# MUX.net
KiCad netlist of a schematic drawn in EAGLE
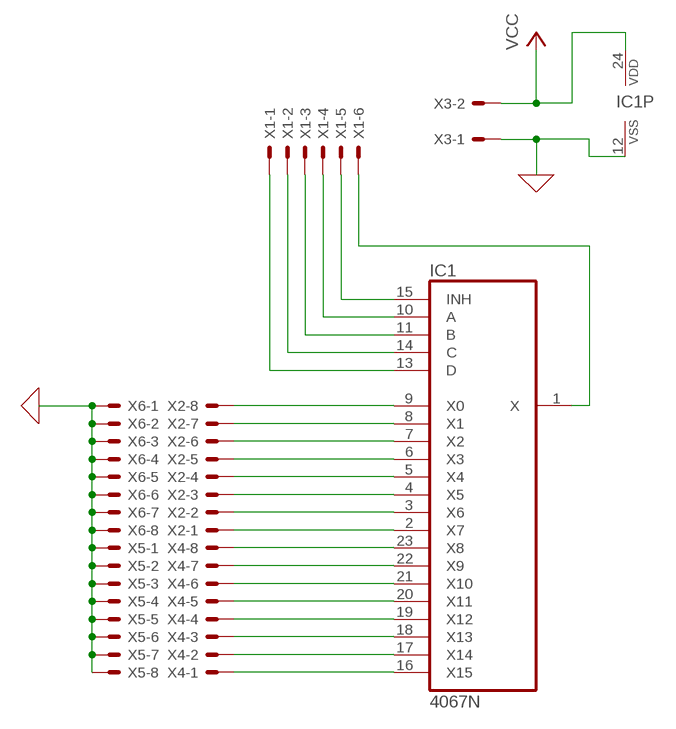
[diagram p0: schematic, sheet 1]

(export (version "E")
  (design (tool "Eeschema 10.0.6"))
  (components
    (comp (ref "IC1")
      (value "4067N")
      (footprint "eagle-import:DIL24-6")
      (libsource (lib "eagle-import") (part "4067N"))
    )
    (comp (ref "X1")
      (value "KK-156-6")
      (footprint "eagle-import:KK-156-6")
      (fields (field (name "MF") "MOLEX"))
      (libsource (lib "eagle-import") (part "KK-156-6"))
    )
    (comp (ref "X2")
      (value "KK-156-8")
      (footprint "eagle-import:KK-156-8")
      (fields (field (name "MF") "MOLEX"))
      (libsource (lib "eagle-import") (part "KK-156-8"))
    )
    (comp (ref "X3")
      (value "KK-156-2")
      (footprint "eagle-import:KK-156-2")
      (fields (field (name "MF") "MOLEX"))
      (libsource (lib "eagle-import") (part "KK-156-2"))
    )
    (comp (ref "X4")
      (value "KK-156-8")
      (footprint "eagle-import:KK-156-8")
      (fields (field (name "MF") "MOLEX"))
      (libsource (lib "eagle-import") (part "KK-156-8"))
    )
    (comp (ref "X5")
      (value "KK-156-8")
      (footprint "eagle-import:KK-156-8")
      (fields (field (name "MF") "MOLEX"))
      (libsource (lib "eagle-import") (part "KK-156-8"))
    )
    (comp (ref "X6")
      (value "KK-156-8")
      (footprint "eagle-import:KK-156-8")
      (fields (field (name "MF") "MOLEX"))
      (libsource (lib "eagle-import") (part "KK-156-8"))
    )
  )
  (nets
    (net (code "1") (name "GND") (class "Default")
      (node (ref "IC1") (pin "12") (pinfunction "VSS_12") (pintype "power_in"))
      (node (ref "X3") (pin "1") (pinfunction "S_1") (pintype "passive"))
      (node (ref "X5") (pin "1") (pinfunction "S_1") (pintype "passive"))
      (node (ref "X5") (pin "2") (pinfunction "S_2") (pintype "passive"))
      (node (ref "X5") (pin "3") (pinfunction "S_3") (pintype "passive"))
      (node (ref "X5") (pin "4") (pinfunction "S_4") (pintype "passive"))
      (node (ref "X5") (pin "5") (pinfunction "S_5") (pintype "passive"))
      (node (ref "X5") (pin "6") (pinfunction "S_6") (pintype "passive"))
      (node (ref "X5") (pin "7") (pinfunction "S_7") (pintype "passive"))
      (node (ref "X5") (pin "8") (pinfunction "S_8") (pintype "passive"))
      (node (ref "X6") (pin "1") (pinfunction "S_1") (pintype "passive"))
      (node (ref "X6") (pin "2") (pinfunction "S_2") (pintype "passive"))
      (node (ref "X6") (pin "3") (pinfunction "S_3") (pintype "passive"))
      (node (ref "X6") (pin "4") (pinfunction "S_4") (pintype "passive"))
      (node (ref "X6") (pin "5") (pinfunction "S_5") (pintype "passive"))
      (node (ref "X6") (pin "6") (pinfunction "S_6") (pintype "passive"))
      (node (ref "X6") (pin "7") (pinfunction "S_7") (pintype "passive"))
      (node (ref "X6") (pin "8") (pinfunction "S_8") (pintype "passive"))
    )
    (net (code "2") (name "Net-(IC1A-A)") (class "Default")
      (node (ref "IC1") (pin "10") (pinfunction "A_10") (pintype "input"))
      (node (ref "X1") (pin "4") (pinfunction "S_4") (pintype "passive"))
    )
    (net (code "3") (name "Net-(IC1A-B)") (class "Default")
      (node (ref "IC1") (pin "11") (pinfunction "B_11") (pintype "input"))
      (node (ref "X1") (pin "3") (pinfunction "S_3") (pintype "passive"))
    )
    (net (code "4") (name "Net-(IC1A-C)") (class "Default")
      (node (ref "IC1") (pin "14") (pinfunction "C_14") (pintype "input"))
      (node (ref "X1") (pin "2") (pinfunction "S_2") (pintype "passive"))
    )
    (net (code "5") (name "Net-(IC1A-D)") (class "Default")
      (node (ref "IC1") (pin "13") (pinfunction "D_13") (pintype "input"))
      (node (ref "X1") (pin "1") (pinfunction "S_1") (pintype "passive"))
    )
    (net (code "6") (name "Net-(IC1A-INH)") (class "Default")
      (node (ref "IC1") (pin "15") (pinfunction "INH_15") (pintype "input"))
      (node (ref "X1") (pin "5") (pinfunction "S_5") (pintype "passive"))
    )
    (net (code "7") (name "Net-(IC1A-X)") (class "Default")
      (node (ref "IC1") (pin "1") (pinfunction "X_1") (pintype "output"))
      (node (ref "X1") (pin "6") (pinfunction "S_6") (pintype "passive"))
    )
    (net (code "8") (name "Net-(IC1A-X0)") (class "Default")
      (node (ref "IC1") (pin "9") (pinfunction "X0_9") (pintype "input"))
      (node (ref "X2") (pin "8") (pinfunction "S_8") (pintype "passive"))
    )
    (net (code "9") (name "Net-(IC1A-X1)") (class "Default")
      (node (ref "IC1") (pin "8") (pinfunction "X1_8") (pintype "input"))
      (node (ref "X2") (pin "7") (pinfunction "S_7") (pintype "passive"))
    )
    (net (code "10") (name "Net-(IC1A-X2)") (class "Default")
      (node (ref "IC1") (pin "7") (pinfunction "X2_7") (pintype "input"))
      (node (ref "X2") (pin "6") (pinfunction "S_6") (pintype "passive"))
    )
    (net (code "11") (name "Net-(IC1A-X3)") (class "Default")
      (node (ref "IC1") (pin "6") (pinfunction "X3_6") (pintype "input"))
      (node (ref "X2") (pin "5") (pinfunction "S_5") (pintype "passive"))
    )
    (net (code "12") (name "Net-(IC1A-X4)") (class "Default")
      (node (ref "IC1") (pin "5") (pinfunction "X4_5") (pintype "input"))
      (node (ref "X2") (pin "4") (pinfunction "S_4") (pintype "passive"))
    )
    (net (code "13") (name "Net-(IC1A-X5)") (class "Default")
      (node (ref "IC1") (pin "4") (pinfunction "X5_4") (pintype "input"))
      (node (ref "X2") (pin "3") (pinfunction "S_3") (pintype "passive"))
    )
    (net (code "14") (name "Net-(IC1A-X6)") (class "Default")
      (node (ref "IC1") (pin "3") (pinfunction "X6_3") (pintype "input"))
      (node (ref "X2") (pin "2") (pinfunction "S_2") (pintype "passive"))
    )
    (net (code "15") (name "Net-(IC1A-X7)") (class "Default")
      (node (ref "IC1") (pin "2") (pinfunction "X7_2") (pintype "input"))
      (node (ref "X2") (pin "1") (pinfunction "S_1") (pintype "passive"))
    )
    (net (code "16") (name "Net-(IC1A-X8)") (class "Default")
      (node (ref "IC1") (pin "23") (pinfunction "X8_23") (pintype "input"))
      (node (ref "X4") (pin "8") (pinfunction "S_8") (pintype "passive"))
    )
    (net (code "17") (name "Net-(IC1A-X9)") (class "Default")
      (node (ref "IC1") (pin "22") (pinfunction "X9_22") (pintype "input"))
      (node (ref "X4") (pin "7") (pinfunction "S_7") (pintype "passive"))
    )
    (net (code "18") (name "Net-(IC1A-X10)") (class "Default")
      (node (ref "IC1") (pin "21") (pinfunction "X10_21") (pintype "input"))
      (node (ref "X4") (pin "6") (pinfunction "S_6") (pintype "passive"))
    )
    (net (code "19") (name "Net-(IC1A-X11)") (class "Default")
      (node (ref "IC1") (pin "20") (pinfunction "X11_20") (pintype "input"))
      (node (ref "X4") (pin "5") (pinfunction "S_5") (pintype "passive"))
    )
    (net (code "20") (name "Net-(IC1A-X12)") (class "Default")
      (node (ref "IC1") (pin "19") (pinfunction "X12_19") (pintype "input"))
      (node (ref "X4") (pin "4") (pinfunction "S_4") (pintype "passive"))
    )
    (net (code "21") (name "Net-(IC1A-X13)") (class "Default")
      (node (ref "IC1") (pin "18") (pinfunction "X13_18") (pintype "input"))
      (node (ref "X4") (pin "3") (pinfunction "S_3") (pintype "passive"))
    )
    (net (code "22") (name "Net-(IC1A-X14)") (class "Default")
      (node (ref "IC1") (pin "17") (pinfunction "X14_17") (pintype "input"))
      (node (ref "X4") (pin "2") (pinfunction "S_2") (pintype "passive"))
    )
    (net (code "23") (name "Net-(IC1A-X15)") (class "Default")
      (node (ref "IC1") (pin "16") (pinfunction "X15_16") (pintype "input"))
      (node (ref "X4") (pin "1") (pinfunction "S_1") (pintype "passive"))
    )
    (net (code "24") (name "VCC") (class "Default")
      (node (ref "IC1") (pin "24") (pinfunction "VDD_24") (pintype "power_in"))
      (node (ref "X3") (pin "2") (pinfunction "S_2") (pintype "passive"))
    )
  )
)
